# RC_PCB.net
KiCad netlist of a schematic drawn in EasyEDA
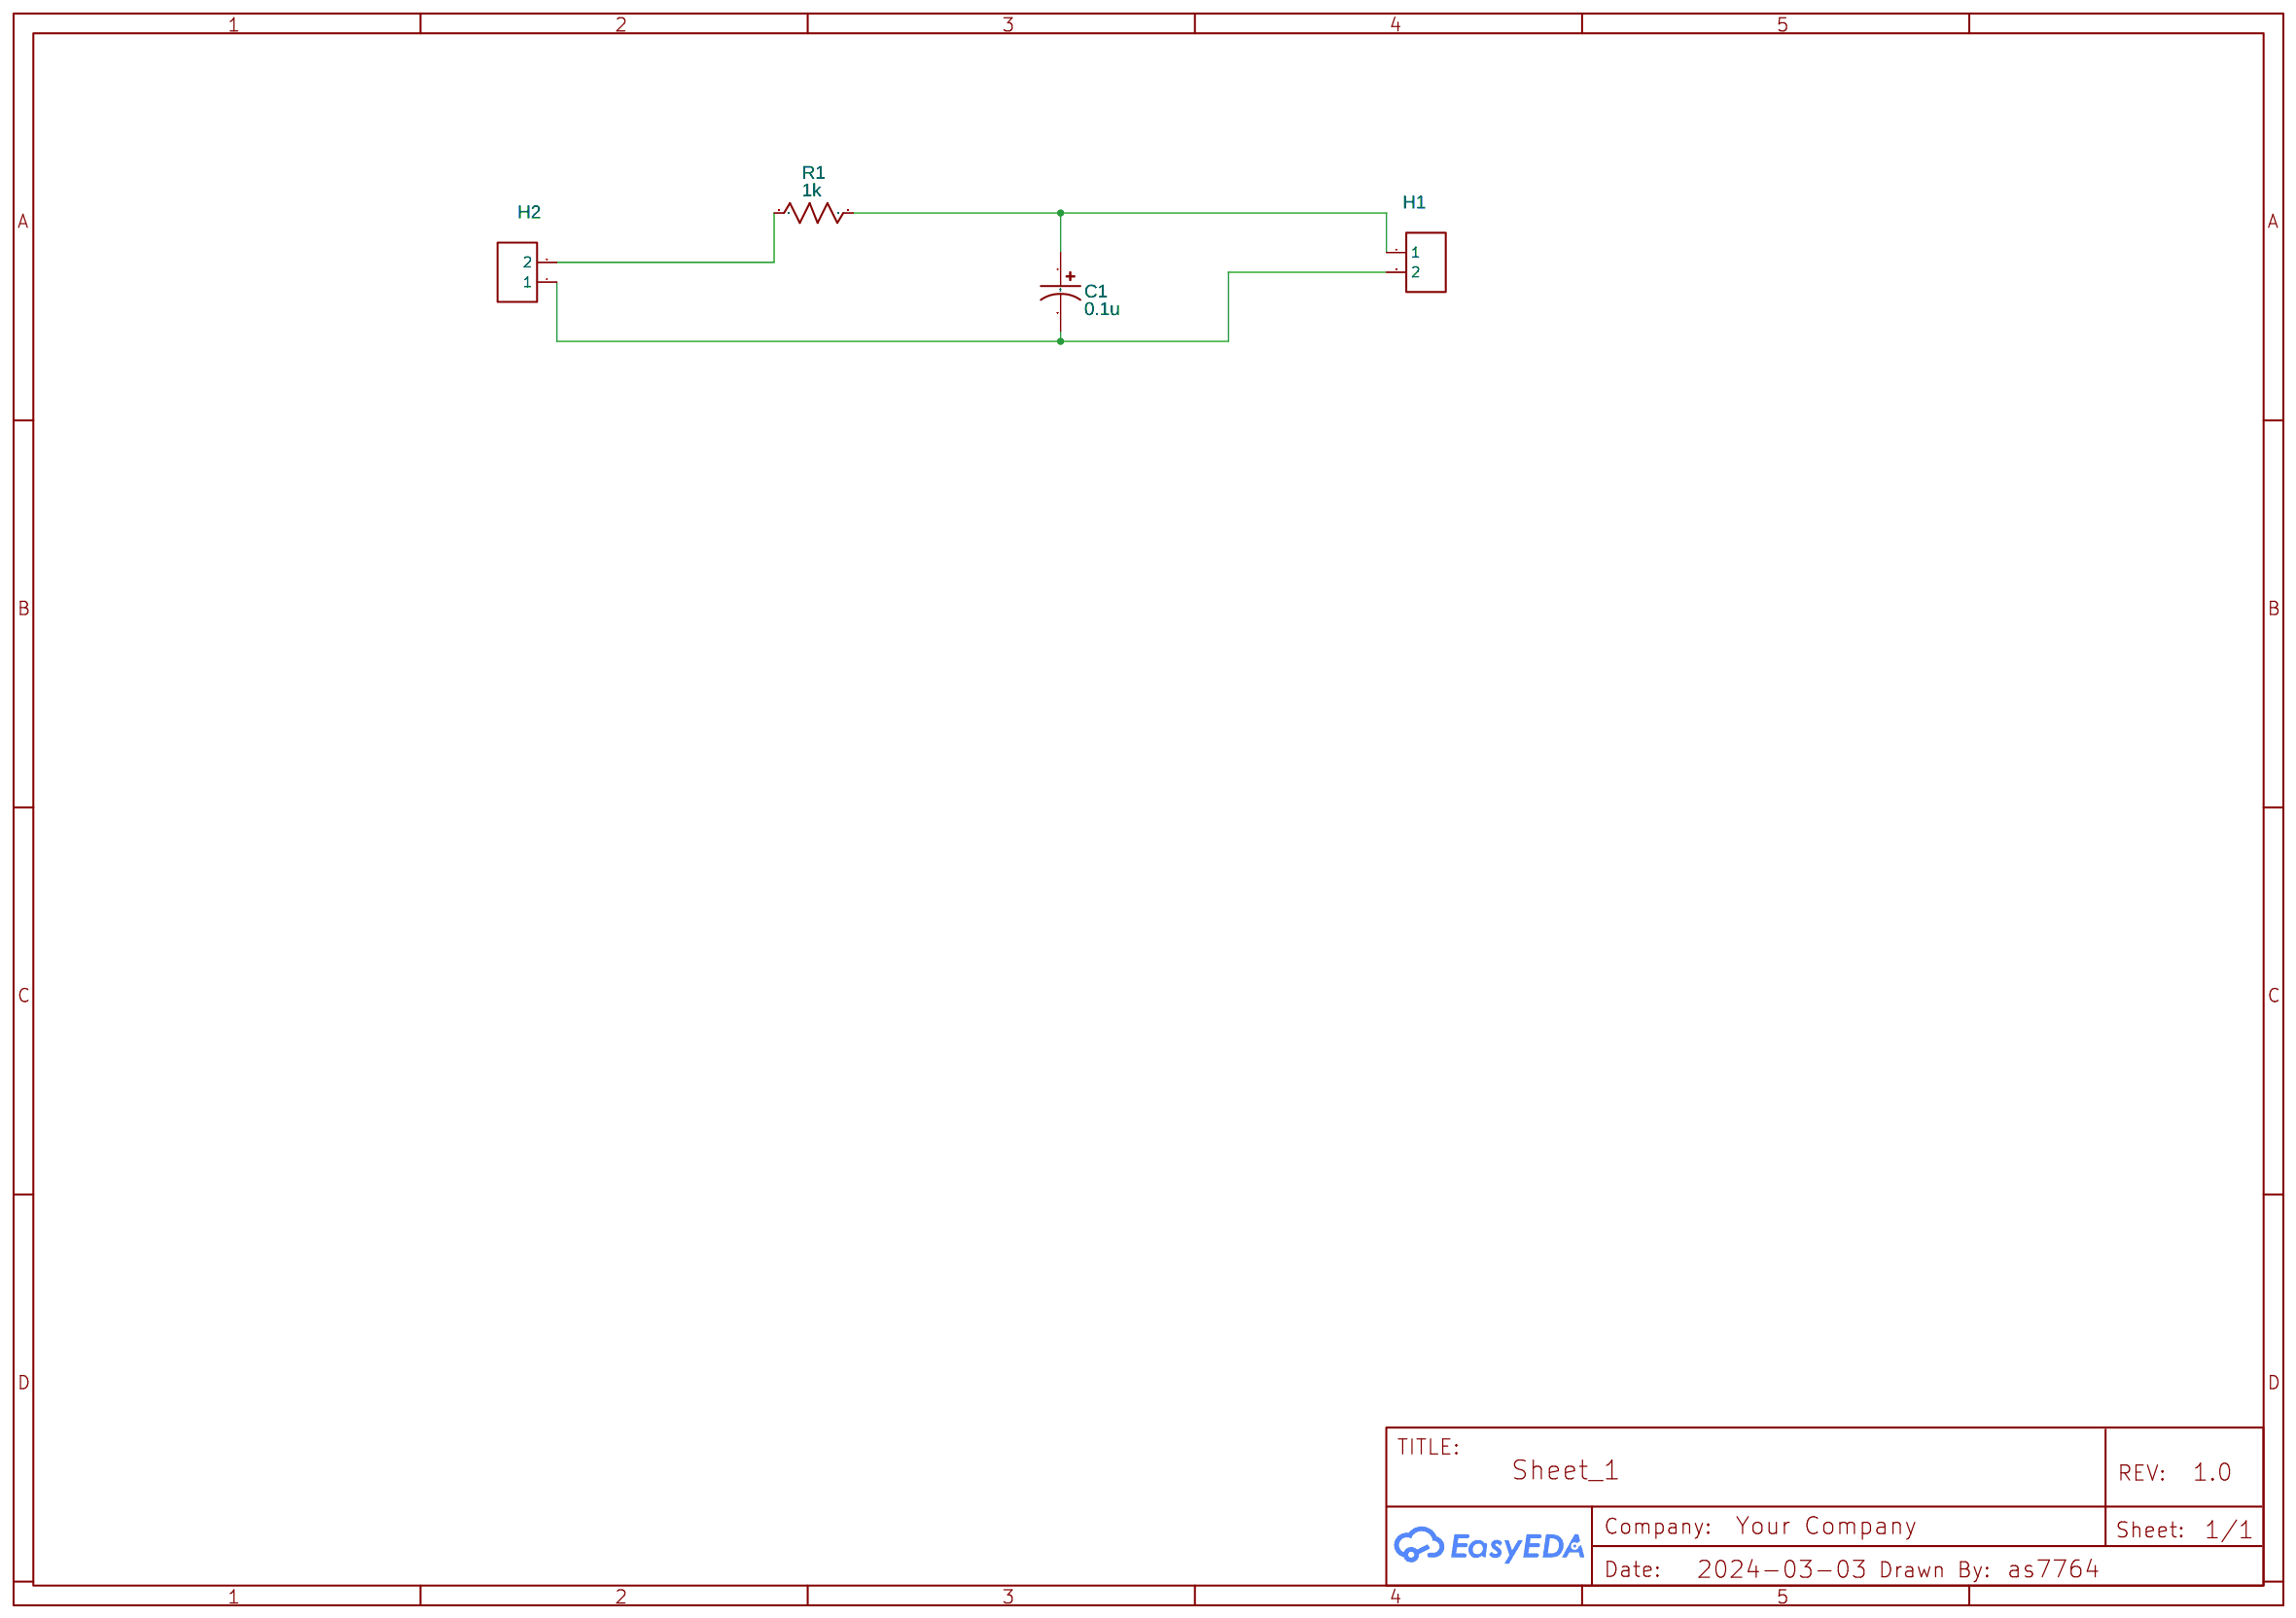
[diagram p0: schematic sheet]

(export (version "E")
  (design (tool "Eeschema 10.0.6"))
  (components
    (comp (ref "C1") (value "0.1u") (libsource (lib "") (part "CE_TH_D3.0×F1.5_US")))
    (comp (ref "H1") (value "HDR-F-2.54_1x2") (libsource (lib "") (part "HDR-F-2.54_1x2")))
    (comp (ref "H2") (value "HDR-F-2.54_1x2") (libsource (lib "") (part "HDR-F-2.54_1x2_1")))
    (comp (ref "R1") (value "1k") (libsource (lib "") (part "R_AXIAL-0.3_US")))
  )
  (nets
    (net (code "1") (name "Net-(C1-Pad1)") (class "Default")
      (node (ref "C1") (pin "1") (pinfunction "1_1") (pintype "unspecified"))
      (node (ref "H1") (pin "1") (pinfunction "1_1") (pintype "input"))
      (node (ref "R1") (pin "2") (pinfunction "2_2") (pintype "unspecified"))
    )
    (net (code "2") (name "Net-(C1-Pad2)") (class "Default")
      (node (ref "C1") (pin "2") (pinfunction "2_2") (pintype "unspecified"))
      (node (ref "H1") (pin "2") (pinfunction "2_2") (pintype "input"))
      (node (ref "H2") (pin "1") (pinfunction "1_1") (pintype "input"))
    )
    (net (code "3") (name "Net-(H2-Pad2)") (class "Default")
      (node (ref "H2") (pin "2") (pinfunction "2_2") (pintype "input"))
      (node (ref "R1") (pin "1") (pinfunction "1_1") (pintype "unspecified"))
    )
  )
)
